# asset-tracker-v007.net
KiCad netlist of a schematic drawn in EAGLE
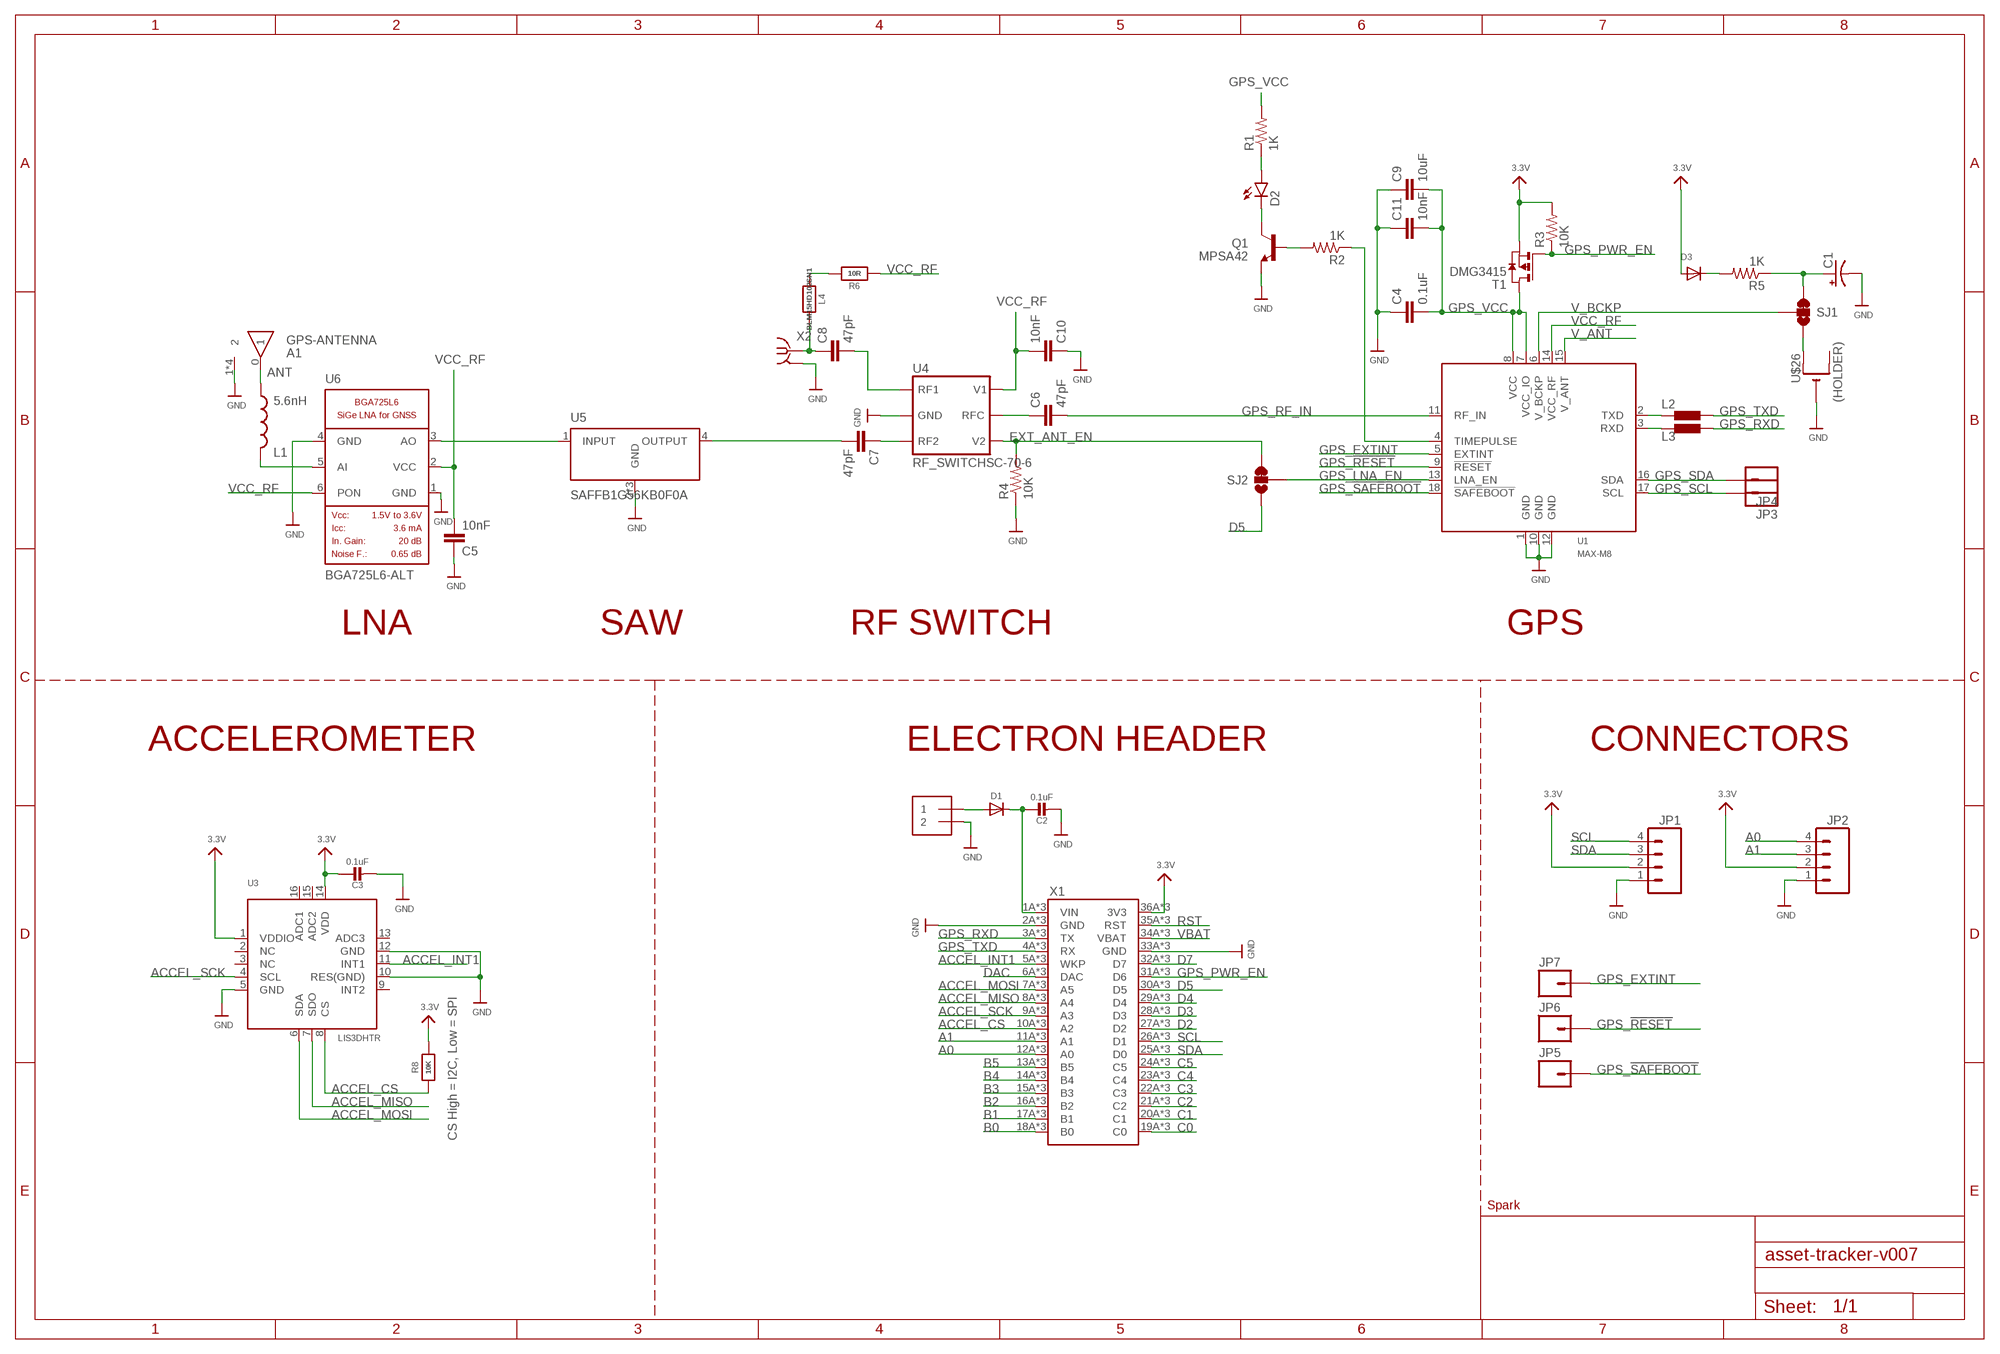
[diagram p0: schematic, sheet 1]

(export (version "E")
  (design (tool "Eeschema 10.0.6"))
  (components
    (comp (ref "A1")
      (value "GPS-ANTENNA")
      (footprint "eagle-import:ANT1818B00BT1516S")
      (libsource (lib "eagle-import") (part "GPS-ANTENNA"))
    )
    (comp (ref "C1")
      (value "SUPERCAP")
      (footprint "eagle-import:414-VA5R")
      (libsource (lib "eagle-import") (part "SUPERCAP"))
    )
    (comp (ref "C2")
      (value "0.1uF")
      (footprint "eagle-import:_0402MP")
      (libsource (lib "eagle-import") (part "CAP_CERAMIC_0402MP"))
    )
    (comp (ref "C3")
      (value "0.1uF")
      (footprint "eagle-import:_0402MP")
      (libsource (lib "eagle-import") (part "CAP_CERAMIC_0402MP"))
    )
    (comp (ref "C4")
      (value "0.1uF")
      (footprint "eagle-import:C0402")
      (libsource (lib "eagle-import") (part "C-EUC0402"))
    )
    (comp (ref "C5")
      (value "10nF")
      (footprint "eagle-import:C0402")
      (libsource (lib "eagle-import") (part "C-EUC0402"))
    )
    (comp (ref "C6")
      (value "47pF")
      (footprint "eagle-import:C0201")
      (libsource (lib "eagle-import") (part "C-EUC0201"))
    )
    (comp (ref "C7")
      (value "47pF")
      (footprint "eagle-import:C0201")
      (libsource (lib "eagle-import") (part "C-EUC0201"))
    )
    (comp (ref "C8")
      (value "47pF")
      (footprint "eagle-import:C0201")
      (libsource (lib "eagle-import") (part "C-EUC0201"))
    )
    (comp (ref "C9")
      (value "10uF")
      (footprint "eagle-import:C0402")
      (libsource (lib "eagle-import") (part "C-EUC0402"))
    )
    (comp (ref "C10")
      (value "10nF")
      (footprint "eagle-import:C0402")
      (libsource (lib "eagle-import") (part "C-EUC0402"))
    )
    (comp (ref "C11")
      (value "10nF")
      (footprint "eagle-import:C0402")
      (libsource (lib "eagle-import") (part "C-EUC0402"))
    )
    (comp (ref "D1")
      (value "DIODESMA")
      (footprint "eagle-import:SMADIODE")
      (libsource (lib "eagle-import") (part "microbuilder_DIODESMA"))
    )
    (comp (ref "D2")
      (value "LED0603")
      (footprint "eagle-import:LED-0603")
      (libsource (lib "eagle-import") (part "LED0603"))
    )
    (comp (ref "D3")
      (value "DIODESOD-523")
      (footprint "eagle-import:SOD-523")
      (libsource (lib "eagle-import") (part "DIODESOD-523"))
    )
    (comp (ref "J1")
      (value "1X2-3.5MM")
      (footprint "eagle-import:1X2-3.5MM")
      (libsource (lib "eagle-import") (part "1X2-3.5MM"))
    )
    (comp (ref "JP1")
      (value "M04JST-PTH-VERT")
      (footprint "eagle-import:JST-4-PTH-VERT")
      (libsource (lib "eagle-import") (part "M04JST-PTH-VERT"))
    )
    (comp (ref "JP2")
      (value "M04JST-PTH-VERT")
      (footprint "eagle-import:JST-4-PTH-VERT")
      (libsource (lib "eagle-import") (part "M04JST-PTH-VERT"))
    )
    (comp (ref "JP3")
      (value "M01SMD-4.5X1.5")
      (footprint "eagle-import:PAD-1.5X4.5")
      (libsource (lib "eagle-import") (part "M01SMD-4.5X1.5"))
    )
    (comp (ref "JP4")
      (value "M01SMD-4.5X1.5")
      (footprint "eagle-import:PAD-1.5X4.5")
      (libsource (lib "eagle-import") (part "M01SMD-4.5X1.5"))
    )
    (comp (ref "JP5")
      (value "M01SMD-4.5X1.5")
      (footprint "eagle-import:PAD-1.5X4.5")
      (libsource (lib "eagle-import") (part "M01SMD-4.5X1.5"))
    )
    (comp (ref "JP6")
      (value "M01SMD-4.5X1.5")
      (footprint "eagle-import:PAD-1.5X4.5")
      (libsource (lib "eagle-import") (part "M01SMD-4.5X1.5"))
    )
    (comp (ref "JP7")
      (value "M01SMD-4.5X1.5")
      (footprint "eagle-import:PAD-1.5X4.5")
      (libsource (lib "eagle-import") (part "M01SMD-4.5X1.5"))
    )
    (comp (ref "L1")
      (value "5.6nH")
      (footprint "eagle-import:C0402")
      (libsource (lib "eagle-import") (part "INDUCTOR0402"))
    )
    (comp (ref "L2")
      (value "BLM15HD102SN1")
      (footprint "eagle-import:0402")
      (libsource (lib "eagle-import") (part "BLM15HD102SN1"))
    )
    (comp (ref "L3")
      (value "BLM15HD102SN1")
      (footprint "eagle-import:0402")
      (libsource (lib "eagle-import") (part "BLM15HD102SN1"))
    )
    (comp (ref "L4")
      (value "BLM15HD102SN1")
      (footprint "eagle-import:_0402MP")
      (libsource (lib "eagle-import") (part "RESISTOR_0402MP"))
    )
    (comp (ref "Q1")
      (value "MPSA42")
      (footprint "eagle-import:SOT23-3")
      (libsource (lib "eagle-import") (part "TRANSISTOR_NPNMPSA42"))
    )
    (comp (ref "R1")
      (value "1K")
      (footprint "eagle-import:R0402")
      (libsource (lib "eagle-import") (part "R-US_R0402"))
    )
    (comp (ref "R2")
      (value "1K")
      (footprint "eagle-import:R0402")
      (libsource (lib "eagle-import") (part "R-US_R0402"))
    )
    (comp (ref "R3")
      (value "10K")
      (footprint "eagle-import:R0402")
      (libsource (lib "eagle-import") (part "R-US_R0402"))
    )
    (comp (ref "R4")
      (value "10K")
      (footprint "eagle-import:R0402")
      (libsource (lib "eagle-import") (part "R-US_R0402"))
    )
    (comp (ref "R5")
      (value "1K")
      (footprint "eagle-import:R0402")
      (libsource (lib "eagle-import") (part "R-US_R0402"))
    )
    (comp (ref "R6")
      (value "10R")
      (footprint "eagle-import:_0402MP")
      (libsource (lib "eagle-import") (part "RESISTOR_0402MP"))
    )
    (comp (ref "R8")
      (value "10K")
      (footprint "eagle-import:_0402MP")
      (libsource (lib "eagle-import") (part "RESISTOR_0402MP"))
    )
    (comp (ref "SJ1")
      (value "JUMPER-PAD-3-2OF3_NC_BY_TRACE_LARGE")
      (footprint "eagle-import:PAD-JUMPER-3-2OF3_NC_BY_TRACE_YES_SILK_LARGE")
      (libsource (lib "eagle-import") (part "JUMPER-PAD-3-2OF3_NC_BY_TRACE_LARGE"))
    )
    (comp (ref "SJ2")
      (value "JUMPER-PAD-3-2OF3_NC_BY_TRACE_LARGE")
      (footprint "eagle-import:PAD-JUMPER-3-2OF3_NC_BY_TRACE_YES_SILK_LARGE")
      (libsource (lib "eagle-import") (part "JUMPER-PAD-3-2OF3_NC_BY_TRACE_LARGE"))
    )
    (comp (ref "T1")
      (value "DMG3415")
      (footprint "eagle-import:SOT-23")
      (libsource (lib "eagle-import") (part "PMOSSOT23"))
    )
    (comp (ref "U$26")
      (value "CR2032SMT")
      (footprint "eagle-import:CR2032-SMD")
      (libsource (lib "eagle-import") (part "CR2032SMT"))
    )
    (comp (ref "U$31")
      (value "SPARK_LOGO")
      (footprint "eagle-import:SPARK_LOGO_TSTOP")
      (libsource (lib "eagle-import") (part "SPARK_LOGO"))
    )
    (comp (ref "U1")
      (value "MAX-M8")
      (footprint "eagle-import:MAX-M8")
      (libsource (lib "eagle-import") (part "MAX-M8"))
    )
    (comp (ref "U3")
      (value "LIS3DHTR")
      (footprint "eagle-import:LGA16_3X3MM")
      (libsource (lib "eagle-import") (part "ACCEL_LIS3DHTR"))
    )
    (comp (ref "U4")
      (value "RF_SWITCHSC-70-6")
      (footprint "eagle-import:SC70-6")
      (libsource (lib "eagle-import") (part "RF_SWITCHSC-70-6"))
    )
    (comp (ref "U5")
      (value "SAFFB1G56KB0F0A")
      (footprint "eagle-import:QCS5I")
      (libsource (lib "eagle-import") (part "FILTERS"))
    )
    (comp (ref "U6")
      (value "BGA725L6-ALT")
      (footprint "eagle-import:LNA-TSLP-6-2-ALT")
      (libsource (lib "eagle-import") (part "BGA725L6-ALT"))
    )
    (comp (ref "X1")
      (value "ELECTRON")
      (footprint "eagle-import:ELECTRON_SMT")
      (libsource (lib "eagle-import") (part "ELECTRON_SMT"))
    )
    (comp (ref "X2")
      (value "IPEX-20279-001E")
      (footprint "eagle-import:IPEX-20279-001E")
      (libsource (lib "eagle-import") (part "IPEX-20279-001E"))
    )
  )
  (nets
    (net (code "1") (name "/A0") (class "Default")
      (node (ref "JP2") (pin "4") (pinfunction "4_4") (pintype "passive"))
      (node (ref "X1") (pin "12A") (pinfunction "A0_12A") (pintype "bidirectional"))
      (node (ref "X1") (pin "12B") (pinfunction "A0_12B") (pintype "bidirectional"))
      (node (ref "X1") (pin "12C") (pinfunction "A0_12C") (pintype "bidirectional"))
    )
    (net (code "2") (name "/A1") (class "Default")
      (node (ref "JP2") (pin "3") (pinfunction "3_3") (pintype "passive"))
      (node (ref "X1") (pin "11A") (pinfunction "A1_11A") (pintype "bidirectional"))
      (node (ref "X1") (pin "11B") (pinfunction "A1_11B") (pintype "bidirectional"))
      (node (ref "X1") (pin "11C") (pinfunction "A1_11C") (pintype "bidirectional"))
    )
    (net (code "3") (name "/ACCEL_CS") (class "Default")
      (node (ref "R8") (pin "1") (pinfunction "1_1") (pintype "passive"))
      (node (ref "U3") (pin "8") (pinfunction "CS_8") (pintype "input"))
      (node (ref "X1") (pin "10A") (pinfunction "A2_10A") (pintype "bidirectional"))
      (node (ref "X1") (pin "10B") (pinfunction "A2_10B") (pintype "bidirectional"))
      (node (ref "X1") (pin "10C") (pinfunction "A2_10C") (pintype "bidirectional"))
    )
    (net (code "4") (name "/ACCEL_INT1") (class "Default")
      (node (ref "U3") (pin "11") (pinfunction "INT1_11") (pintype "output"))
      (node (ref "X1") (pin "5A") (pinfunction "WKP_5A") (pintype "bidirectional"))
      (node (ref "X1") (pin "5B") (pinfunction "WKP_5B") (pintype "bidirectional"))
      (node (ref "X1") (pin "5C") (pinfunction "WKP_5C") (pintype "bidirectional"))
    )
    (net (code "5") (name "/ACCEL_MISO") (class "Default")
      (node (ref "U3") (pin "7") (pinfunction "SDO_7") (pintype "bidirectional"))
      (node (ref "X1") (pin "8A") (pinfunction "A4_8A") (pintype "bidirectional"))
      (node (ref "X1") (pin "8B") (pinfunction "A4_8B") (pintype "bidirectional"))
      (node (ref "X1") (pin "8C") (pinfunction "A4_8C") (pintype "bidirectional"))
    )
    (net (code "6") (name "/ACCEL_MOSI") (class "Default")
      (node (ref "U3") (pin "6") (pinfunction "SDA_6") (pintype "bidirectional"))
      (node (ref "X1") (pin "7A") (pinfunction "A5_7A") (pintype "bidirectional"))
      (node (ref "X1") (pin "7B") (pinfunction "A5_7B") (pintype "bidirectional"))
      (node (ref "X1") (pin "7C") (pinfunction "A5_7C") (pintype "bidirectional"))
    )
    (net (code "7") (name "/ACCEL_SCK") (class "Default")
      (node (ref "U3") (pin "4") (pinfunction "SCL_4") (pintype "bidirectional"))
      (node (ref "X1") (pin "9A") (pinfunction "A3_9A") (pintype "bidirectional"))
      (node (ref "X1") (pin "9B") (pinfunction "A3_9B") (pintype "bidirectional"))
      (node (ref "X1") (pin "9C") (pinfunction "A3_9C") (pintype "bidirectional"))
    )
    (net (code "8") (name "/ANT") (class "Default")
      (node (ref "A1") (pin "0") (pinfunction "1_0") (pintype "output"))
      (node (ref "L1") (pin "2") (pinfunction "2_2") (pintype "passive"))
    )
    (net (code "9") (name "/B0") (class "Default")
      (node (ref "X1") (pin "18A") (pinfunction "B0_18A") (pintype "bidirectional"))
      (node (ref "X1") (pin "18B") (pinfunction "B0_18B") (pintype "bidirectional"))
      (node (ref "X1") (pin "18C") (pinfunction "B0_18C") (pintype "bidirectional"))
    )
    (net (code "10") (name "/B1") (class "Default")
      (node (ref "X1") (pin "17A") (pinfunction "B1_17A") (pintype "bidirectional"))
      (node (ref "X1") (pin "17B") (pinfunction "B1_17B") (pintype "bidirectional"))
      (node (ref "X1") (pin "17C") (pinfunction "B1_17C") (pintype "bidirectional"))
    )
    (net (code "11") (name "/B2") (class "Default")
      (node (ref "X1") (pin "16A") (pinfunction "B2_16A") (pintype "bidirectional"))
      (node (ref "X1") (pin "16B") (pinfunction "B2_16B") (pintype "bidirectional"))
      (node (ref "X1") (pin "16C") (pinfunction "B2_16C") (pintype "bidirectional"))
    )
    (net (code "12") (name "/B3") (class "Default")
      (node (ref "X1") (pin "15A") (pinfunction "B3_15A") (pintype "bidirectional"))
      (node (ref "X1") (pin "15B") (pinfunction "B3_15B") (pintype "bidirectional"))
      (node (ref "X1") (pin "15C") (pinfunction "B3_15C") (pintype "bidirectional"))
    )
    (net (code "13") (name "/B4") (class "Default")
      (node (ref "X1") (pin "14A") (pinfunction "B4_14A") (pintype "bidirectional"))
      (node (ref "X1") (pin "14B") (pinfunction "B4_14B") (pintype "bidirectional"))
      (node (ref "X1") (pin "14C") (pinfunction "B4_14C") (pintype "bidirectional"))
    )
    (net (code "14") (name "/B5") (class "Default")
      (node (ref "X1") (pin "13A") (pinfunction "B5_13A") (pintype "bidirectional"))
      (node (ref "X1") (pin "13B") (pinfunction "B5_13B") (pintype "bidirectional"))
      (node (ref "X1") (pin "13C") (pinfunction "B5_13C") (pintype "bidirectional"))
    )
    (net (code "15") (name "/C0") (class "Default")
      (node (ref "X1") (pin "19A") (pinfunction "C0_19A") (pintype "bidirectional"))
      (node (ref "X1") (pin "19B") (pinfunction "C0_19B") (pintype "bidirectional"))
      (node (ref "X1") (pin "19C") (pinfunction "C0_19C") (pintype "bidirectional"))
    )
    (net (code "16") (name "/C1") (class "Default")
      (node (ref "X1") (pin "20A") (pinfunction "C1_20A") (pintype "bidirectional"))
      (node (ref "X1") (pin "20B") (pinfunction "C1_20B") (pintype "bidirectional"))
      (node (ref "X1") (pin "20C") (pinfunction "C1_20C") (pintype "bidirectional"))
    )
    (net (code "17") (name "/C2") (class "Default")
      (node (ref "X1") (pin "21A") (pinfunction "C2_21A") (pintype "bidirectional"))
      (node (ref "X1") (pin "21B") (pinfunction "C2_21B") (pintype "bidirectional"))
      (node (ref "X1") (pin "21C") (pinfunction "C2_21C") (pintype "bidirectional"))
    )
    (net (code "18") (name "/C3") (class "Default")
      (node (ref "X1") (pin "22A") (pinfunction "C3_22A") (pintype "bidirectional"))
      (node (ref "X1") (pin "22B") (pinfunction "C3_22B") (pintype "bidirectional"))
      (node (ref "X1") (pin "22C") (pinfunction "C3_22C") (pintype "bidirectional"))
    )
    (net (code "19") (name "/C4") (class "Default")
      (node (ref "X1") (pin "23A") (pinfunction "C4_23A") (pintype "bidirectional"))
      (node (ref "X1") (pin "23B") (pinfunction "C4_23B") (pintype "bidirectional"))
      (node (ref "X1") (pin "23C") (pinfunction "C4_23C") (pintype "bidirectional"))
    )
    (net (code "20") (name "/C5") (class "Default")
      (node (ref "X1") (pin "24A") (pinfunction "C5_24A") (pintype "bidirectional"))
      (node (ref "X1") (pin "24B") (pinfunction "C5_24B") (pintype "bidirectional"))
      (node (ref "X1") (pin "24C") (pinfunction "C5_24C") (pintype "bidirectional"))
    )
    (net (code "21") (name "/D2") (class "Default")
      (node (ref "X1") (pin "27A") (pinfunction "D2_27A") (pintype "bidirectional"))
      (node (ref "X1") (pin "27B") (pinfunction "D2_27B") (pintype "bidirectional"))
      (node (ref "X1") (pin "27C") (pinfunction "D2_27C") (pintype "bidirectional"))
    )
    (net (code "22") (name "/D3") (class "Default")
      (node (ref "X1") (pin "28A") (pinfunction "D3_28A") (pintype "bidirectional"))
      (node (ref "X1") (pin "28B") (pinfunction "D3_28B") (pintype "bidirectional"))
      (node (ref "X1") (pin "28C") (pinfunction "D3_28C") (pintype "bidirectional"))
    )
    (net (code "23") (name "/D4") (class "Default")
      (node (ref "X1") (pin "29A") (pinfunction "D4_29A") (pintype "bidirectional"))
      (node (ref "X1") (pin "29B") (pinfunction "D4_29B") (pintype "bidirectional"))
      (node (ref "X1") (pin "29C") (pinfunction "D4_29C") (pintype "bidirectional"))
    )
    (net (code "24") (name "/D5") (class "Default")
      (node (ref "SJ2") (pin "1") (pinfunction "1_1") (pintype "passive"))
      (node (ref "X1") (pin "30A") (pinfunction "D5_30A") (pintype "bidirectional"))
      (node (ref "X1") (pin "30B") (pinfunction "D5_30B") (pintype "bidirectional"))
      (node (ref "X1") (pin "30C") (pinfunction "D5_30C") (pintype "bidirectional"))
    )
    (net (code "25") (name "/D7") (class "Default")
      (node (ref "X1") (pin "32A") (pinfunction "D7_32A") (pintype "bidirectional"))
      (node (ref "X1") (pin "32B") (pinfunction "D7_32B") (pintype "bidirectional"))
      (node (ref "X1") (pin "32C") (pinfunction "D7_32C") (pintype "bidirectional"))
    )
    (net (code "26") (name "/DAC") (class "Default")
      (node (ref "X1") (pin "6A") (pinfunction "DAC_6A") (pintype "bidirectional"))
      (node (ref "X1") (pin "6B") (pinfunction "DAC_6B") (pintype "bidirectional"))
      (node (ref "X1") (pin "6C") (pinfunction "DAC_6C") (pintype "bidirectional"))
    )
    (net (code "27") (name "/EXT_ANT_EN") (class "Default")
      (node (ref "R4") (pin "2") (pinfunction "2_2") (pintype "passive"))
      (node (ref "SJ2") (pin "3") (pinfunction "3_3") (pintype "passive"))
      (node (ref "U4") (pin "4") (pinfunction "V2_4") (pintype "input"))
    )
    (net (code "28") (name "/GPS_EXTINT") (class "Default")
      (node (ref "JP7") (pin "P$1") (pinfunction "1_P$1") (pintype "passive"))
      (node (ref "U1") (pin "5") (pinfunction "EXTINT_5") (pintype "bidirectional"))
    )
    (net (code "29") (name "/GPS_LNA_EN") (class "Default")
      (node (ref "SJ2") (pin "2") (pinfunction "2_2") (pintype "passive"))
      (node (ref "U1") (pin "13") (pinfunction "LNA_EN_13") (pintype "bidirectional"))
    )
    (net (code "30") (name "/GPS_PWR_EN") (class "Default")
      (node (ref "R3") (pin "1") (pinfunction "1_1") (pintype "passive"))
      (node (ref "T1") (pin "3") (pinfunction "G_3") (pintype "passive"))
      (node (ref "X1") (pin "31A") (pinfunction "D6_31A") (pintype "bidirectional"))
      (node (ref "X1") (pin "31B") (pinfunction "D6_31B") (pintype "bidirectional"))
      (node (ref "X1") (pin "31C") (pinfunction "D6_31C") (pintype "bidirectional"))
    )
    (net (code "31") (name "/GPS_RF_IN") (class "Default")
      (node (ref "C6") (pin "2") (pinfunction "2_2") (pintype "passive"))
      (node (ref "U1") (pin "11") (pinfunction "RF_IN_11") (pintype "bidirectional"))
    )
    (net (code "32") (name "/GPS_RXD") (class "Default")
      (node (ref "L3") (pin "2") (pinfunction "2_2") (pintype "passive"))
      (node (ref "X1") (pin "3A") (pinfunction "TX_3A") (pintype "bidirectional"))
      (node (ref "X1") (pin "3B") (pinfunction "TX_3B") (pintype "bidirectional"))
      (node (ref "X1") (pin "3C") (pinfunction "TX_3C") (pintype "bidirectional"))
    )
    (net (code "33") (name "/GPS_SCL") (class "Default")
      (node (ref "JP3") (pin "P$1") (pinfunction "1_P$1") (pintype "passive"))
      (node (ref "U1") (pin "17") (pinfunction "SCL_17") (pintype "bidirectional"))
    )
    (net (code "34") (name "/GPS_SDA") (class "Default")
      (node (ref "JP4") (pin "P$1") (pinfunction "1_P$1") (pintype "passive"))
      (node (ref "U1") (pin "16") (pinfunction "SDA_16") (pintype "bidirectional"))
    )
    (net (code "35") (name "/GPS_TXD") (class "Default")
      (node (ref "L2") (pin "2") (pinfunction "2_2") (pintype "passive"))
      (node (ref "X1") (pin "4A") (pinfunction "RX_4A") (pintype "bidirectional"))
      (node (ref "X1") (pin "4B") (pinfunction "RX_4B") (pintype "bidirectional"))
      (node (ref "X1") (pin "4C") (pinfunction "RX_4C") (pintype "bidirectional"))
    )
    (net (code "36") (name "/GPS_VCC") (class "Default")
      (node (ref "C11") (pin "2") (pinfunction "2_2") (pintype "passive"))
      (node (ref "C4") (pin "2") (pinfunction "2_2") (pintype "passive"))
      (node (ref "C9") (pin "2") (pinfunction "2_2") (pintype "passive"))
      (node (ref "R1") (pin "2") (pinfunction "2_2") (pintype "passive"))
      (node (ref "T1") (pin "1") (pinfunction "D_1") (pintype "passive"))
      (node (ref "U1") (pin "7") (pinfunction "VCC_IO_7") (pintype "bidirectional"))
      (node (ref "U1") (pin "8") (pinfunction "VCC_8") (pintype "bidirectional"))
    )
    (net (code "37") (name "/GPS_~{RESET}") (class "Default")
      (node (ref "JP6") (pin "P$1") (pinfunction "1_P$1") (pintype "passive"))
      (node (ref "U1") (pin "9") (pinfunction "~{RESET}_9") (pintype "bidirectional"))
    )
    (net (code "38") (name "/GPS_~{SAFEBOOT}") (class "Default")
      (node (ref "JP5") (pin "P$1") (pinfunction "1_P$1") (pintype "passive"))
      (node (ref "U1") (pin "18") (pinfunction "~{SAFEBOOT}_18") (pintype "bidirectional"))
    )
    (net (code "39") (name "/RST") (class "Default")
      (node (ref "X1") (pin "35A") (pinfunction "RST_35A") (pintype "bidirectional"))
      (node (ref "X1") (pin "35B") (pinfunction "RST_35B") (pintype "bidirectional"))
      (node (ref "X1") (pin "35C") (pinfunction "RST_35C") (pintype "bidirectional"))
    )
    (net (code "40") (name "/SCL") (class "Default")
      (node (ref "JP1") (pin "4") (pinfunction "4_4") (pintype "passive"))
      (node (ref "X1") (pin "26A") (pinfunction "D1_26A") (pintype "bidirectional"))
      (node (ref "X1") (pin "26B") (pinfunction "D1_26B") (pintype "bidirectional"))
      (node (ref "X1") (pin "26C") (pinfunction "D1_26C") (pintype "bidirectional"))
    )
    (net (code "41") (name "/SDA") (class "Default")
      (node (ref "JP1") (pin "3") (pinfunction "3_3") (pintype "passive"))
      (node (ref "X1") (pin "25A") (pinfunction "D0_25A") (pintype "bidirectional"))
      (node (ref "X1") (pin "25B") (pinfunction "D0_25B") (pintype "bidirectional"))
      (node (ref "X1") (pin "25C") (pinfunction "D0_25C") (pintype "bidirectional"))
    )
    (net (code "42") (name "/VBAT") (class "Default")
      (node (ref "X1") (pin "34A") (pinfunction "VBAT_34A") (pintype "passive"))
      (node (ref "X1") (pin "34B") (pinfunction "VBAT_34B") (pintype "passive"))
      (node (ref "X1") (pin "34C") (pinfunction "VBAT_34C") (pintype "passive"))
    )
    (net (code "43") (name "/VCC_RF") (class "Default")
      (node (ref "C10") (pin "2") (pinfunction "2_2") (pintype "passive"))
      (node (ref "C5") (pin "2") (pinfunction "2_2") (pintype "passive"))
      (node (ref "R6") (pin "1") (pinfunction "1_1") (pintype "passive"))
      (node (ref "U1") (pin "14") (pinfunction "VCC_RF_14") (pintype "bidirectional"))
      (node (ref "U4") (pin "6") (pinfunction "V1_6") (pintype "input"))
      (node (ref "U6") (pin "2") (pinfunction "VCC_2") (pintype "power_in"))
      (node (ref "U6") (pin "6") (pinfunction "PON_6") (pintype "input"))
    )
    (net (code "44") (name "/V_ANT") (class "Default")
      (node (ref "U1") (pin "15") (pinfunction "V_ANT_15") (pintype "bidirectional"))
    )
    (net (code "45") (name "/V_BCKP") (class "Default")
      (node (ref "SJ1") (pin "2") (pinfunction "2_2") (pintype "passive"))
      (node (ref "U1") (pin "6") (pinfunction "V_BCKP_6") (pintype "bidirectional"))
    )
    (net (code "46") (name "3.3V") (class "Default")
      (node (ref "C3") (pin "1") (pinfunction "1_1") (pintype "passive"))
      (node (ref "D3") (pin "A") (pinfunction "A_A") (pintype "passive"))
      (node (ref "JP1") (pin "2") (pinfunction "2_2") (pintype "passive"))
      (node (ref "JP2") (pin "2") (pinfunction "2_2") (pintype "passive"))
      (node (ref "R3") (pin "2") (pinfunction "2_2") (pintype "passive"))
      (node (ref "R8") (pin "2") (pinfunction "2_2") (pintype "passive"))
      (node (ref "T1") (pin "2") (pinfunction "S_2") (pintype "passive"))
      (node (ref "U3") (pin "1") (pinfunction "VDDIO_1") (pintype "power_in"))
      (node (ref "U3") (pin "14") (pinfunction "VDD_14") (pintype "power_in"))
      (node (ref "X1") (pin "36A") (pinfunction "3V3_36A") (pintype "power_in"))
      (node (ref "X1") (pin "36B") (pinfunction "3V3_36B") (pintype "power_in"))
      (node (ref "X1") (pin "36C") (pinfunction "3V3_36C") (pintype "power_in"))
    )
    (net (code "47") (name "GND") (class "Default")
      (node (ref "A1") (pin "1") (pinfunction "2_1") (pintype "power_in"))
      (node (ref "A1") (pin "2") (pinfunction "2_2") (pintype "power_in"))
      (node (ref "A1") (pin "3") (pinfunction "2_3") (pintype "power_in"))
      (node (ref "A1") (pin "4") (pinfunction "2_4") (pintype "power_in"))
      (node (ref "C1") (pin "-") (pinfunction "-_-") (pintype "passive"))
      (node (ref "C10") (pin "1") (pinfunction "1_1") (pintype "passive"))
      (node (ref "C11") (pin "1") (pinfunction "1_1") (pintype "passive"))
      (node (ref "C2") (pin "2") (pinfunction "2_2") (pintype "passive"))
      (node (ref "C3") (pin "2") (pinfunction "2_2") (pintype "passive"))
      (node (ref "C4") (pin "1") (pinfunction "1_1") (pintype "passive"))
      (node (ref "C5") (pin "1") (pinfunction "1_1") (pintype "passive"))
      (node (ref "C9") (pin "1") (pinfunction "1_1") (pintype "passive"))
      (node (ref "J1") (pin "2") (pinfunction "2_2") (pintype "passive"))
      (node (ref "JP1") (pin "1") (pinfunction "1_1") (pintype "passive"))
      (node (ref "JP2") (pin "1") (pinfunction "1_1") (pintype "passive"))
      (node (ref "Q1") (pin "2") (pinfunction "E_2") (pintype "passive"))
      (node (ref "R4") (pin "1") (pinfunction "1_1") (pintype "passive"))
      (node (ref "U$26") (pin "-") (pinfunction "-_-") (pintype "passive"))
      (node (ref "U1") (pin "1") (pinfunction "GND_1") (pintype "bidirectional"))
      (node (ref "U1") (pin "10") (pinfunction "GND_10") (pintype "bidirectional"))
      (node (ref "U1") (pin "12") (pinfunction "GND_12") (pintype "bidirectional"))
      (node (ref "U3") (pin "10") (pinfunction "RES(GND)_10") (pintype "bidirectional"))
      (node (ref "U3") (pin "12") (pinfunction "GND_12") (pintype "power_in"))
      (node (ref "U3") (pin "5") (pinfunction "GND_5") (pintype "power_in"))
      (node (ref "U4") (pin "2") (pinfunction "GND_2") (pintype "power_in"))
      (node (ref "U5") (pin "2") (pinfunction "GND_2") (pintype "power_in"))
      (node (ref "U5") (pin "3") (pinfunction "GND_3") (pintype "power_in"))
      (node (ref "U5") (pin "5") (pinfunction "GND_5") (pintype "power_in"))
      (node (ref "U6") (pin "1") (pinfunction "GND_1") (pintype "power_in"))
      (node (ref "U6") (pin "4") (pinfunction "GND_4") (pintype "power_in"))
      (node (ref "X1") (pin "2A") (pinfunction "GND_2A") (pintype "power_in"))
      (node (ref "X1") (pin "2B") (pinfunction "GND_2B") (pintype "power_in"))
      (node (ref "X1") (pin "2C") (pinfunction "GND_2C") (pintype "power_in"))
      (node (ref "X1") (pin "33A") (pinfunction "GND_33A") (pintype "power_in"))
      (node (ref "X1") (pin "33B") (pinfunction "GND_33B") (pintype "power_in"))
      (node (ref "X1") (pin "33C") (pinfunction "GND_33C") (pintype "power_in"))
      (node (ref "X2") (pin "2@1") (pinfunction "GND_2@1") (pintype "passive"))
      (node (ref "X2") (pin "2@2") (pinfunction "GND_2@2") (pintype "passive"))
    )
    (net (code "48") (name "Net-(C1-Pad+)") (class "Default")
      (node (ref "C1") (pin "+") (pinfunction "+_+") (pintype "passive"))
      (node (ref "R5") (pin "1") (pinfunction "1_1") (pintype "passive"))
      (node (ref "SJ1") (pin "3") (pinfunction "3_3") (pintype "passive"))
    )
    (net (code "49") (name "Net-(C2-Pad1)") (class "Default")
      (node (ref "C2") (pin "1") (pinfunction "1_1") (pintype "passive"))
      (node (ref "D1") (pin "C") (pinfunction "C_C") (pintype "passive"))
      (node (ref "X1") (pin "1A") (pinfunction "VIN_1A") (pintype "power_in"))
      (node (ref "X1") (pin "1B") (pinfunction "VIN_1B") (pintype "power_in"))
      (node (ref "X1") (pin "1C") (pinfunction "VIN_1C") (pintype "power_in"))
    )
    (net (code "50") (name "Net-(C8-Pad1)") (class "Default")
      (node (ref "C8") (pin "1") (pinfunction "1_1") (pintype "passive"))
      (node (ref "L4") (pin "2") (pinfunction "2_2") (pintype "passive"))
      (node (ref "X2") (pin "1") (pinfunction "1_1") (pintype "passive"))
    )
    (net (code "51") (name "Net-(D1-PadA)") (class "Default")
      (node (ref "D1") (pin "A") (pinfunction "A_A") (pintype "passive"))
      (node (ref "J1") (pin "1") (pinfunction "1_1") (pintype "passive"))
    )
    (net (code "52") (name "Net-(D2-PadA)") (class "Default")
      (node (ref "D2") (pin "A") (pinfunction "A_A") (pintype "passive"))
      (node (ref "R1") (pin "1") (pinfunction "1_1") (pintype "passive"))
    )
    (net (code "53") (name "Net-(D3-C)") (class "Default")
      (node (ref "D3") (pin "K") (pinfunction "C_K") (pintype "passive"))
      (node (ref "R5") (pin "2") (pinfunction "2_2") (pintype "passive"))
    )
    (net (code "54") (name "Net-(L4-Pad1)") (class "Default")
      (node (ref "L4") (pin "1") (pinfunction "1_1") (pintype "passive"))
      (node (ref "R6") (pin "2") (pinfunction "2_2") (pintype "passive"))
    )
    (net (code "55") (name "Net-(Q1-B)") (class "Default")
      (node (ref "Q1") (pin "1") (pinfunction "B_1") (pintype "passive"))
      (node (ref "R2") (pin "2") (pinfunction "2_2") (pintype "passive"))
    )
    (net (code "56") (name "Net-(Q1-C)") (class "Default")
      (node (ref "D2") (pin "C") (pinfunction "C_C") (pintype "passive"))
      (node (ref "Q1") (pin "3") (pinfunction "C_3") (pintype "passive"))
    )
    (net (code "57") (name "Net-(U$26-+)") (class "Default")
      (node (ref "SJ1") (pin "1") (pinfunction "1_1") (pintype "passive"))
      (node (ref "U$26") (pin "+$1") (pinfunction "+_+$1") (pintype "passive"))
    )
    (net (code "58") (name "Net-(U1-RXD)") (class "Default")
      (node (ref "L3") (pin "1") (pinfunction "1_1") (pintype "passive"))
      (node (ref "U1") (pin "3") (pinfunction "RXD_3") (pintype "bidirectional"))
    )
    (net (code "59") (name "Net-(U1-TIMEPULSE)") (class "Default")
      (node (ref "R2") (pin "1") (pinfunction "1_1") (pintype "passive"))
      (node (ref "U1") (pin "4") (pinfunction "TIMEPULSE_4") (pintype "bidirectional"))
    )
    (net (code "60") (name "Net-(U1-TXD)") (class "Default")
      (node (ref "L2") (pin "1") (pinfunction "1_1") (pintype "passive"))
      (node (ref "U1") (pin "2") (pinfunction "TXD_2") (pintype "bidirectional"))
    )
    (net (code "61") (name "Net-(U4-RF1)") (class "Default")
      (node (ref "C8") (pin "2") (pinfunction "2_2") (pintype "passive"))
      (node (ref "U4") (pin "1") (pinfunction "RF1_1") (pintype "output"))
    )
    (net (code "62") (name "Net-(U4-RF2)") (class "Default")
      (node (ref "C7") (pin "1") (pinfunction "1_1") (pintype "passive"))
      (node (ref "U4") (pin "3") (pinfunction "RF2_3") (pintype "output"))
    )
    (net (code "63") (name "Net-(U4-RFC)") (class "Default")
      (node (ref "C6") (pin "1") (pinfunction "1_1") (pintype "passive"))
      (node (ref "U4") (pin "5") (pinfunction "RFC_5") (pintype "input"))
    )
    (net (code "64") (name "Net-(U5-INPUT)") (class "Default")
      (node (ref "U5") (pin "1") (pinfunction "INPUT_1") (pintype "input"))
      (node (ref "U6") (pin "3") (pinfunction "AO_3") (pintype "output"))
    )
    (net (code "65") (name "Net-(U5-OUTPUT)") (class "Default")
      (node (ref "C7") (pin "2") (pinfunction "2_2") (pintype "passive"))
      (node (ref "U5") (pin "4") (pinfunction "OUTPUT_4") (pintype "bidirectional"))
    )
    (net (code "66") (name "Net-(U6-AI)") (class "Default")
      (node (ref "L1") (pin "1") (pinfunction "1_1") (pintype "passive"))
      (node (ref "U6") (pin "5") (pinfunction "AI_5") (pintype "input"))
    )
    (net (code "67") (name "unconnected-(U$26-+1-Pad+$2)") (class "Default")
      (node (ref "U$26") (pin "+$2") (pinfunction "+1_+$2") (pintype "passive"))
    )
    (net (code "68") (name "unconnected-(U3-ADC1-Pad16)") (class "Default")
      (node (ref "U3") (pin "16") (pinfunction "ADC1_16") (pintype "input"))
    )
    (net (code "69") (name "unconnected-(U3-ADC2-Pad15)") (class "Default")
      (node (ref "U3") (pin "15") (pinfunction "ADC2_15") (pintype "input"))
    )
    (net (code "70") (name "unconnected-(U3-ADC3-Pad13)") (class "Default")
      (node (ref "U3") (pin "13") (pinfunction "ADC3_13") (pintype "input"))
    )
    (net (code "71") (name "unconnected-(U3-INT2-Pad9)") (class "Default")
      (node (ref "U3") (pin "9") (pinfunction "INT2_9") (pintype "output"))
    )
    (net (code "72") (name "unconnected-(U3-NC-Pad2)") (class "Default")
      (node (ref "U3") (pin "2") (pinfunction "NC_2") (pintype "no_connect"))
    )
    (net (code "73") (name "unconnected-(U3-NC-Pad3)") (class "Default")
      (node (ref "U3") (pin "3") (pinfunction "NC_3") (pintype "no_connect"))
    )
  )
)
